# SBC_65C02_ISA_IRQ_v2.net
KiCad netlist of a schematic drawn in EAGLE
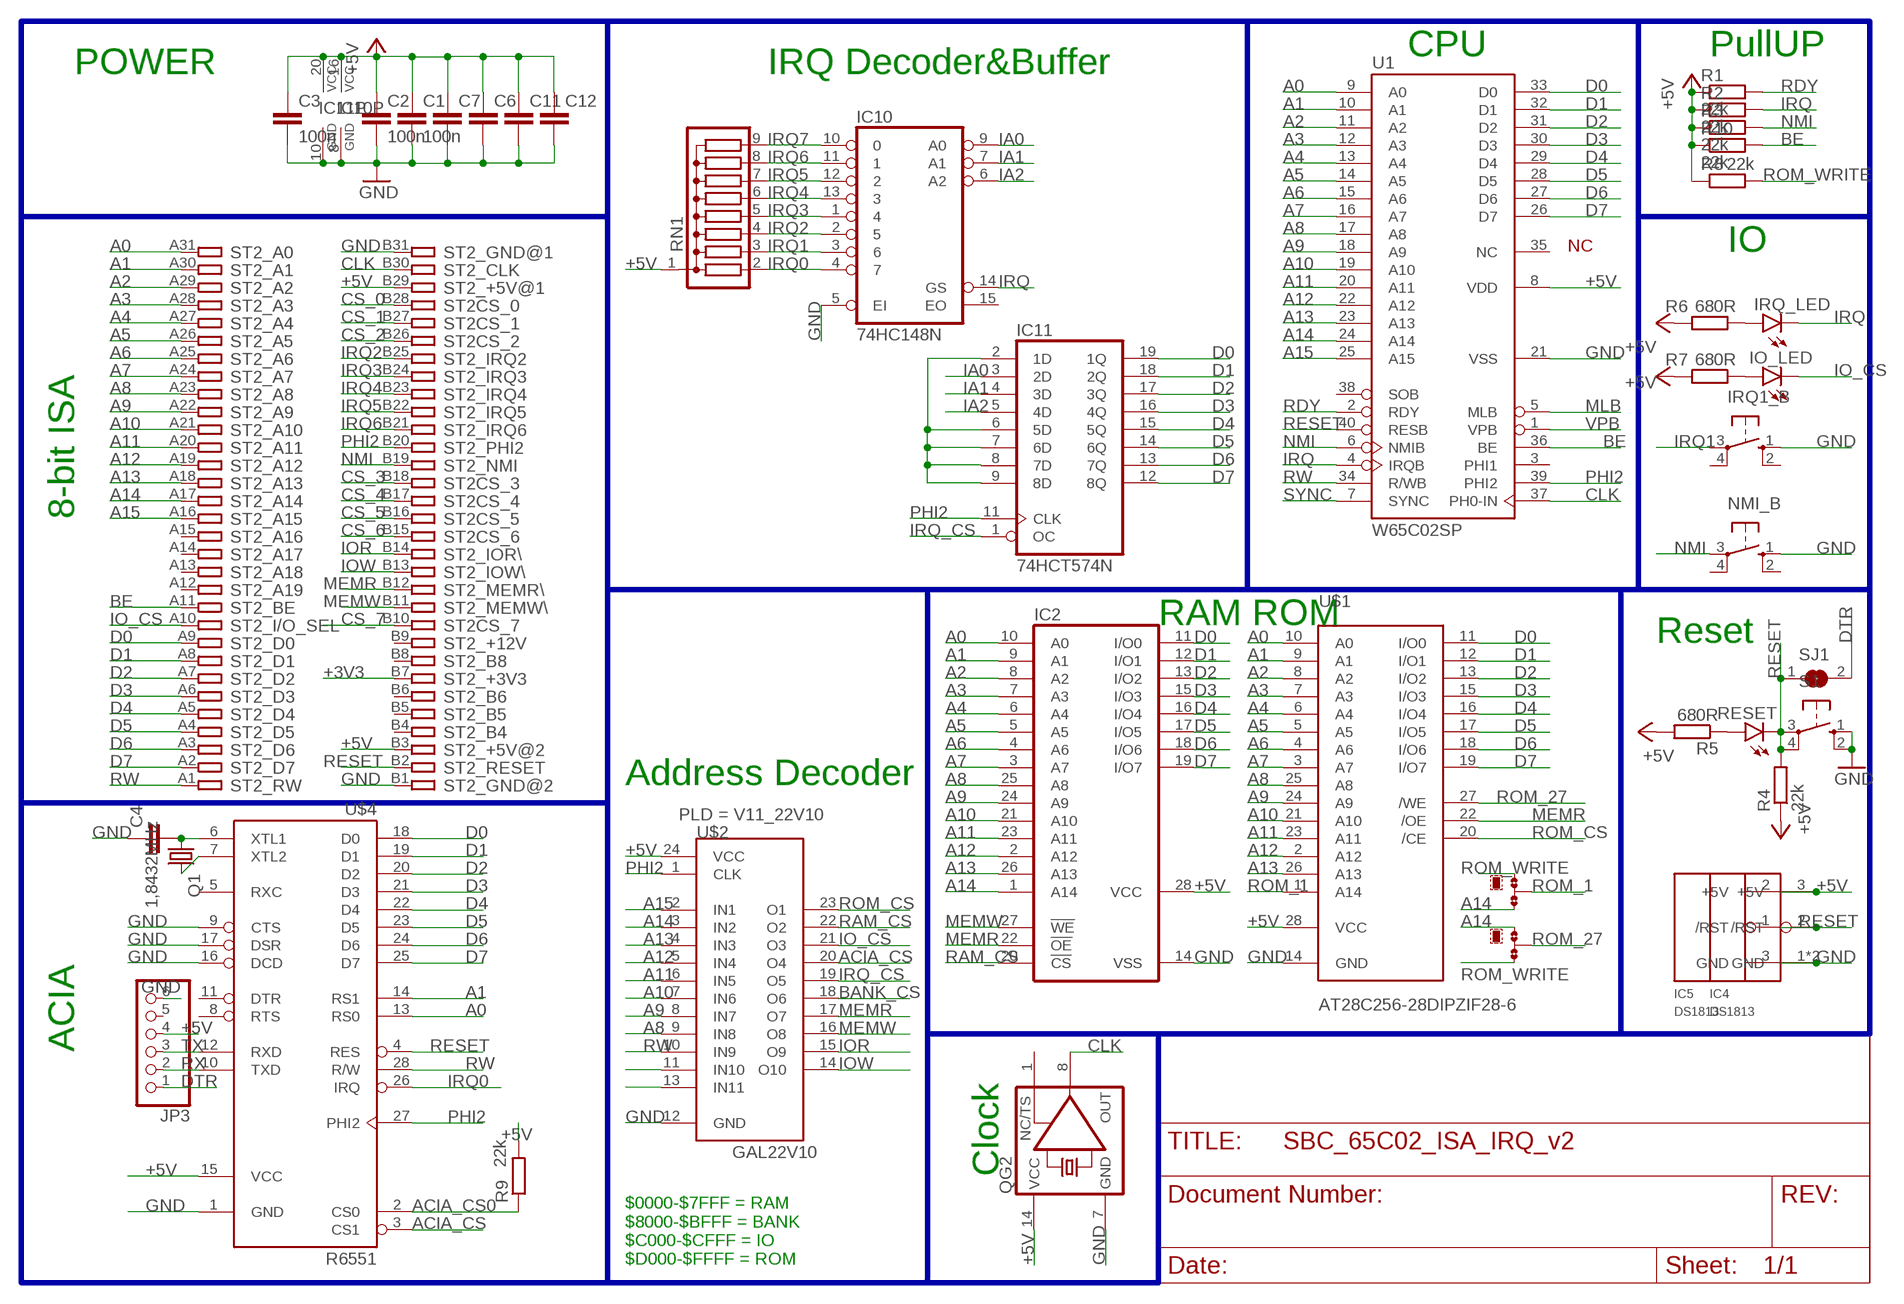
[diagram p0: schematic, sheet 1]

(export (version "E")
  (design (tool "Eeschema 10.0.6"))
  (components
    (comp (ref "C1")
      (value "100n")
      (footprint "eagle-import:C050-025X075")
      (libsource (lib "eagle-import") (part "C-EU050-025X075"))
    )
    (comp (ref "C2")
      (value "100n")
      (footprint "eagle-import:C050-025X075")
      (libsource (lib "eagle-import") (part "C-EU050-025X075"))
    )
    (comp (ref "C3")
      (value "100n")
      (footprint "eagle-import:C050-025X075")
      (libsource (lib "eagle-import") (part "C-EU050-025X075"))
    )
    (comp (ref "C4")
      (value "C-EU025-030X050")
      (footprint "eagle-import:C025-030X050")
      (libsource (lib "eagle-import") (part "rcl_334_C-EU025-030X050"))
    )
    (comp (ref "C6")
      (value "C-EU050-035X075")
      (footprint "eagle-import:C050-035X075")
      (libsource (lib "eagle-import") (part "rcl_334_C-EU050-035X075"))
    )
    (comp (ref "C7")
      (value "C-EU050-035X075")
      (footprint "eagle-import:C050-035X075")
      (libsource (lib "eagle-import") (part "rcl_334_C-EU050-035X075"))
    )
    (comp (ref "C11")
      (value "C-EU050-035X075")
      (footprint "eagle-import:C050-035X075")
      (libsource (lib "eagle-import") (part "rcl_334_C-EU050-035X075"))
    )
    (comp (ref "C12")
      (value "C-EU050-035X075")
      (footprint "eagle-import:C050-035X075")
      (libsource (lib "eagle-import") (part "rcl_334_C-EU050-035X075"))
    )
    (comp (ref "IC2")
      (value "62256P")
      (footprint "eagle-import:DIL28-6")
      (libsource (lib "eagle-import") (part "62256P"))
    )
    (comp (ref "IC4")
      (value "DS1813")
      (footprint "eagle-import:SOT223")
      (libsource (lib "eagle-import") (part "DS1813SOT-223"))
    )
    (comp (ref "IC5")
      (value "DS1813")
      (footprint "eagle-import:TO-92")
      (libsource (lib "eagle-import") (part "DS1813"))
    )
    (comp (ref "IC10")
      (value "74HC148N")
      (footprint "eagle-import:DIL16")
      (libsource (lib "eagle-import") (part "74148NHC"))
    )
    (comp (ref "IC11")
      (value "74HCT574N")
      (footprint "eagle-import:DIL20")
      (libsource (lib "eagle-import") (part "74574NHCT"))
    )
    (comp (ref "IO_LED")
      (value "LED5MM")
      (footprint "eagle-import:LED5MM")
      (libsource (lib "eagle-import") (part "LED5MM"))
    )
    (comp (ref "IRQ1_B")
      (value "10-XX")
      (footprint "eagle-import:B3F-10XX")
      (fields (field (name "MPN") "B3F-1000"))
      (libsource (lib "eagle-import") (part "10-XX"))
    )
    (comp (ref "IRQ_LED")
      (value "LED5MM")
      (footprint "eagle-import:LED5MM")
      (libsource (lib "eagle-import") (part "LED5MM"))
    )
    (comp (ref "JP3")
      (value "PINHD-1X6/90")
      (footprint "eagle-import:1X06_90")
      (libsource (lib "eagle-import") (part "PINHD-1X6/90"))
    )
    (comp (ref "NMI_B")
      (value "10-XX")
      (footprint "eagle-import:B3F-10XX")
      (fields (field (name "MPN") "B3F-1000"))
      (libsource (lib "eagle-import") (part "10-XX"))
    )
    (comp (ref "Q1")
      (value "1,8432MHz")
      (footprint "eagle-import:HC49_S")
      (libsource (lib "eagle-import") (part "CRYSTALHC49S"))
    )
    (comp (ref "QG2")
      (value "XO-14")
      (footprint "eagle-import:DIL14S")
      (libsource (lib "eagle-import") (part "XO-14"))
    )
    (comp (ref "R1")
      (value "22k")
      (footprint "eagle-import:0207_10")
      (libsource (lib "eagle-import") (part "R-EU_0207/10"))
    )
    (comp (ref "R2")
      (value "22k")
      (footprint "eagle-import:0207_10")
      (libsource (lib "eagle-import") (part "R-EU_0207/10"))
    )
    (comp (ref "R3")
      (value "22k")
      (footprint "eagle-import:0207_10")
      (libsource (lib "eagle-import") (part "R-EU_0207/10"))
    )
    (comp (ref "R4")
      (value "22k")
      (footprint "eagle-import:0207_10")
      (libsource (lib "eagle-import") (part "resistor_348_R-EU_0207/10"))
    )
    (comp (ref "R5")
      (value "680R")
      (footprint "eagle-import:0207_10")
      (libsource (lib "eagle-import") (part "resistor_348_R-EU_0207/10"))
    )
    (comp (ref "R6")
      (value "680R")
      (footprint "eagle-import:0207_10")
      (libsource (lib "eagle-import") (part "resistor_348_R-EU_0207/10"))
    )
    (comp (ref "R7")
      (value "680R")
      (footprint "eagle-import:0207_10")
      (libsource (lib "eagle-import") (part "resistor_348_R-EU_0207/10"))
    )
    (comp (ref "R8")
      (value "22k")
      (footprint "eagle-import:0207_10")
      (libsource (lib "eagle-import") (part "rcl_334_R-EU_0207/10"))
    )
    (comp (ref "R9")
      (value "22k")
      (footprint "eagle-import:0207_10")
      (libsource (lib "eagle-import") (part "rcl_334_R-EU_0207/10"))
    )
    (comp (ref "R10")
      (value "22k")
      (footprint "eagle-import:0207_10")
      (libsource (lib "eagle-import") (part "R-EU_0207/10"))
    )
    (comp (ref "RESET")
      (value "LED5MM")
      (footprint "eagle-import:LED5MM")
      (libsource (lib "eagle-import") (part "LED5MM"))
    )
    (comp (ref "RN1")
      (value "G08R")
      (footprint "eagle-import:SIL9")
      (libsource (lib "eagle-import") (part "G08R"))
    )
    (comp (ref "ROM_1")
      (value "0R-JUMPA")
      (footprint "eagle-import:A0R-JMP")
      (libsource (lib "eagle-import") (part "0R-JUMPA"))
    )
    (comp (ref "ROM_27")
      (value "0R-JUMPA")
      (footprint "eagle-import:A0R-JMP")
      (libsource (lib "eagle-import") (part "0R-JUMPA"))
    )
    (comp (ref "S1")
      (value "10-XX")
      (footprint "eagle-import:B3F-10XX")
      (fields (field (name "MPN") "B3F-1000"))
      (libsource (lib "eagle-import") (part "10-XX"))
    )
    (comp (ref "SJ1") (value "SJ") (footprint "eagle-import:SJ") (libsource (lib "eagle-import") (part "SJ")))
    (comp (ref "ST2")
      (value "IBM8BIT_ISASHORT")
      (footprint "eagle-import:APP_2X32_SHORT")
      (libsource (lib "eagle-import") (part "IBM8BIT_ISASHORT"))
    )
    (comp (ref "U$1")
      (value "AT28C256-28DIPZIF28-6")
      (footprint "eagle-import:228-1277-00-0602J")
      (libsource (lib "eagle-import") (part "AT28C256-28DIPZIF28-6"))
    )
    (comp (ref "U$2")
      (value "GAL22V10")
      (footprint "eagle-import:DIL28_1")
      (libsource (lib "eagle-import") (part "GAL22V10"))
    )
    (comp (ref "U$4")
      (value "R6551")
      (footprint "eagle-import:DIP-28")
      (libsource (lib "eagle-import") (part "R6551"))
    )
    (comp (ref "U1")
      (value "W65C02SP")
      (footprint "eagle-import:DIP-40")
      (libsource (lib "eagle-import") (part "W65C02SP"))
    )
  )
  (nets
    (net (code "1") (name "+5V") (class "Default")
      (node (ref "C1") (pin "1") (pinfunction "1_1") (pintype "passive"))
      (node (ref "C11") (pin "1") (pinfunction "1_1") (pintype "passive"))
      (node (ref "C12") (pin "1") (pinfunction "1_1") (pintype "passive"))
      (node (ref "C2") (pin "1") (pinfunction "1_1") (pintype "passive"))
      (node (ref "C3") (pin "1") (pinfunction "1_1") (pintype "passive"))
      (node (ref "C6") (pin "1") (pinfunction "1_1") (pintype "passive"))
      (node (ref "C7") (pin "1") (pinfunction "1_1") (pintype "passive"))
      (node (ref "IC10") (pin "16") (pinfunction "VCC_16") (pintype "power_in"))
      (node (ref "IC11") (pin "20") (pinfunction "VCC_20") (pintype "power_in"))
      (node (ref "IC2") (pin "28") (pinfunction "VCC_28") (pintype "power_in"))
      (node (ref "IC4") (pin "3") (pinfunction "+5V_3") (pintype "power_in"))
      (node (ref "IC5") (pin "2") (pinfunction "+5V_2") (pintype "power_in"))
      (node (ref "JP3") (pin "4") (pinfunction "4_4") (pintype "passive"))
      (node (ref "QG2") (pin "14") (pinfunction "VCC_14") (pintype "power_in"))
      (node (ref "R1") (pin "1") (pinfunction "1_1") (pintype "passive"))
      (node (ref "R10") (pin "1") (pinfunction "1_1") (pintype "passive"))
      (node (ref "R2") (pin "1") (pinfunction "1_1") (pintype "passive"))
      (node (ref "R3") (pin "1") (pinfunction "1_1") (pintype "passive"))
      (node (ref "R4") (pin "1") (pinfunction "1_1") (pintype "passive"))
      (node (ref "R5") (pin "2") (pinfunction "2_2") (pintype "passive"))
      (node (ref "R6") (pin "2") (pinfunction "2_2") (pintype "passive"))
      (node (ref "R7") (pin "2") (pinfunction "2_2") (pintype "passive"))
      (node (ref "R8") (pin "1") (pinfunction "1_1") (pintype "passive"))
      (node (ref "R9") (pin "2") (pinfunction "2_2") (pintype "passive"))
      (node (ref "RN1") (pin "1") (pinfunction "1_1") (pintype "passive"))
      (node (ref "ST2") (pin "B29") (pinfunction "P_B29") (pintype "bidirectional"))
      (node (ref "ST2") (pin "B3") (pinfunction "P_B3") (pintype "bidirectional"))
      (node (ref "U$1") (pin "28") (pinfunction "VCC_28") (pintype "bidirectional"))
      (node (ref "U$2") (pin "24") (pinfunction "VCC_24") (pintype "bidirectional"))
      (node (ref "U$4") (pin "15") (pinfunction "VCC_15") (pintype "power_in"))
      (node (ref "U1") (pin "8") (pinfunction "VDD_8") (pintype "power_in"))
    )
    (net (code "2") (name "/+3V3") (class "Default")
      (node (ref "ST2") (pin "B7") (pinfunction "P_B7") (pintype "bidirectional"))
    )
    (net (code "3") (name "/A0") (class "Default")
      (node (ref "IC2") (pin "10") (pinfunction "A0_10") (pintype "input"))
      (node (ref "ST2") (pin "A31") (pinfunction "P_A31") (pintype "bidirectional"))
      (node (ref "U$1") (pin "10") (pinfunction "A0_10") (pintype "bidirectional"))
      (node (ref "U$4") (pin "13") (pinfunction "RS0_13") (pintype "input"))
      (node (ref "U1") (pin "9") (pinfunction "A0_9") (pintype "bidirectional"))
    )
    (net (code "4") (name "/A1") (class "Default")
      (node (ref "IC2") (pin "9") (pinfunction "A1_9") (pintype "input"))
      (node (ref "ST2") (pin "A30") (pinfunction "P_A30") (pintype "bidirectional"))
      (node (ref "U$1") (pin "9") (pinfunction "A1_9") (pintype "bidirectional"))
      (node (ref "U$4") (pin "14") (pinfunction "RS1_14") (pintype "input"))
      (node (ref "U1") (pin "10") (pinfunction "A1_10") (pintype "bidirectional"))
    )
    (net (code "5") (name "/A2") (class "Default")
      (node (ref "IC2") (pin "8") (pinfunction "A2_8") (pintype "input"))
      (node (ref "ST2") (pin "A29") (pinfunction "P_A29") (pintype "bidirectional"))
      (node (ref "U$1") (pin "8") (pinfunction "A2_8") (pintype "bidirectional"))
      (node (ref "U1") (pin "11") (pinfunction "A2_11") (pintype "bidirectional"))
    )
    (net (code "6") (name "/A3") (class "Default")
      (node (ref "IC2") (pin "7") (pinfunction "A3_7") (pintype "input"))
      (node (ref "ST2") (pin "A28") (pinfunction "P_A28") (pintype "bidirectional"))
      (node (ref "U$1") (pin "7") (pinfunction "A3_7") (pintype "bidirectional"))
      (node (ref "U1") (pin "12") (pinfunction "A3_12") (pintype "bidirectional"))
    )
    (net (code "7") (name "/A4") (class "Default")
      (node (ref "IC2") (pin "6") (pinfunction "A4_6") (pintype "input"))
      (node (ref "ST2") (pin "A27") (pinfunction "P_A27") (pintype "bidirectional"))
      (node (ref "U$1") (pin "6") (pinfunction "A4_6") (pintype "bidirectional"))
      (node (ref "U1") (pin "13") (pinfunction "A4_13") (pintype "bidirectional"))
    )
    (net (code "8") (name "/A5") (class "Default")
      (node (ref "IC2") (pin "5") (pinfunction "A5_5") (pintype "input"))
      (node (ref "ST2") (pin "A26") (pinfunction "P_A26") (pintype "bidirectional"))
      (node (ref "U$1") (pin "5") (pinfunction "A5_5") (pintype "bidirectional"))
      (node (ref "U1") (pin "14") (pinfunction "A5_14") (pintype "bidirectional"))
    )
    (net (code "9") (name "/A6") (class "Default")
      (node (ref "IC2") (pin "4") (pinfunction "A6_4") (pintype "input"))
      (node (ref "ST2") (pin "A25") (pinfunction "P_A25") (pintype "bidirectional"))
      (node (ref "U$1") (pin "4") (pinfunction "A6_4") (pintype "bidirectional"))
      (node (ref "U1") (pin "15") (pinfunction "A6_15") (pintype "bidirectional"))
    )
    (net (code "10") (name "/A7") (class "Default")
      (node (ref "IC2") (pin "3") (pinfunction "A7_3") (pintype "input"))
      (node (ref "ST2") (pin "A24") (pinfunction "P_A24") (pintype "bidirectional"))
      (node (ref "U$1") (pin "3") (pinfunction "A7_3") (pintype "bidirectional"))
      (node (ref "U1") (pin "16") (pinfunction "A7_16") (pintype "bidirectional"))
    )
    (net (code "11") (name "/A8") (class "Default")
      (node (ref "IC2") (pin "25") (pinfunction "A8_25") (pintype "input"))
      (node (ref "ST2") (pin "A23") (pinfunction "P_A23") (pintype "bidirectional"))
      (node (ref "U$1") (pin "25") (pinfunction "A8_25") (pintype "bidirectional"))
      (node (ref "U$2") (pin "9") (pinfunction "IN8_9") (pintype "bidirectional"))
      (node (ref "U1") (pin "17") (pinfunction "A8_17") (pintype "bidirectional"))
    )
    (net (code "12") (name "/A9") (class "Default")
      (node (ref "IC2") (pin "24") (pinfunction "A9_24") (pintype "input"))
      (node (ref "ST2") (pin "A22") (pinfunction "P_A22") (pintype "bidirectional"))
      (node (ref "U$1") (pin "24") (pinfunction "A9_24") (pintype "bidirectional"))
      (node (ref "U$2") (pin "8") (pinfunction "IN7_8") (pintype "bidirectional"))
      (node (ref "U1") (pin "18") (pinfunction "A9_18") (pintype "bidirectional"))
    )
    (net (code "13") (name "/A10") (class "Default")
      (node (ref "IC2") (pin "21") (pinfunction "A10_21") (pintype "input"))
      (node (ref "ST2") (pin "A21") (pinfunction "P_A21") (pintype "bidirectional"))
      (node (ref "U$1") (pin "21") (pinfunction "A10_21") (pintype "bidirectional"))
      (node (ref "U$2") (pin "7") (pinfunction "IN6_7") (pintype "bidirectional"))
      (node (ref "U1") (pin "19") (pinfunction "A10_19") (pintype "bidirectional"))
    )
    (net (code "14") (name "/A11") (class "Default")
      (node (ref "IC2") (pin "23") (pinfunction "A11_23") (pintype "input"))
      (node (ref "ST2") (pin "A20") (pinfunction "P_A20") (pintype "bidirectional"))
      (node (ref "U$1") (pin "23") (pinfunction "A11_23") (pintype "bidirectional"))
      (node (ref "U$2") (pin "6") (pinfunction "IN5_6") (pintype "bidirectional"))
      (node (ref "U1") (pin "20") (pinfunction "A11_20") (pintype "bidirectional"))
    )
    (net (code "15") (name "/A12") (class "Default")
      (node (ref "IC2") (pin "2") (pinfunction "A12_2") (pintype "input"))
      (node (ref "ST2") (pin "A19") (pinfunction "P_A19") (pintype "bidirectional"))
      (node (ref "U$1") (pin "2") (pinfunction "A12_2") (pintype "bidirectional"))
      (node (ref "U$2") (pin "5") (pinfunction "IN4_5") (pintype "bidirectional"))
      (node (ref "U1") (pin "22") (pinfunction "A12_22") (pintype "bidirectional"))
    )
    (net (code "16") (name "/A13") (class "Default")
      (node (ref "IC2") (pin "26") (pinfunction "A13_26") (pintype "input"))
      (node (ref "ST2") (pin "A18") (pinfunction "P_A18") (pintype "bidirectional"))
      (node (ref "U$1") (pin "26") (pinfunction "A13_26") (pintype "bidirectional"))
      (node (ref "U$2") (pin "4") (pinfunction "IN3_4") (pintype "bidirectional"))
      (node (ref "U1") (pin "23") (pinfunction "A13_23") (pintype "bidirectional"))
    )
    (net (code "17") (name "/A14") (class "Default")
      (node (ref "IC2") (pin "1") (pinfunction "A14_1") (pintype "input"))
      (node (ref "ROM_1") (pin "3") (pinfunction "3_3") (pintype "passive"))
      (node (ref "ROM_27") (pin "1") (pinfunction "1_1") (pintype "passive"))
      (node (ref "ST2") (pin "A17") (pinfunction "P_A17") (pintype "bidirectional"))
      (node (ref "U$2") (pin "3") (pinfunction "IN2_3") (pintype "bidirectional"))
      (node (ref "U1") (pin "24") (pinfunction "A14_24") (pintype "bidirectional"))
    )
    (net (code "18") (name "/A15") (class "Default")
      (node (ref "ST2") (pin "A16") (pinfunction "P_A16") (pintype "bidirectional"))
      (node (ref "U$2") (pin "2") (pinfunction "IN1_2") (pintype "bidirectional"))
      (node (ref "U1") (pin "25") (pinfunction "A15_25") (pintype "bidirectional"))
    )
    (net (code "19") (name "/ACIA_CS") (class "Default")
      (node (ref "U$2") (pin "20") (pinfunction "O4_20") (pintype "bidirectional"))
      (node (ref "U$4") (pin "3") (pinfunction "CS1_3") (pintype "input"))
    )
    (net (code "20") (name "/ACIA_CS0") (class "Default")
      (node (ref "R9") (pin "1") (pinfunction "1_1") (pintype "passive"))
      (node (ref "U$4") (pin "2") (pinfunction "CS0_2") (pintype "input"))
    )
    (net (code "21") (name "/BANK_CS") (class "Default")
      (node (ref "U$2") (pin "18") (pinfunction "O6_18") (pintype "bidirectional"))
    )
    (net (code "22") (name "/BE") (class "Default")
      (node (ref "R10") (pin "2") (pinfunction "2_2") (pintype "passive"))
      (node (ref "ST2") (pin "A11") (pinfunction "P_A11") (pintype "bidirectional"))
      (node (ref "U1") (pin "36") (pinfunction "BE_36") (pintype "input"))
    )
    (net (code "23") (name "/CLK") (class "Default")
      (node (ref "QG2") (pin "8") (pinfunction "OUT_8") (pintype "output"))
      (node (ref "ST2") (pin "B30") (pinfunction "P_B30") (pintype "bidirectional"))
      (node (ref "U1") (pin "37") (pinfunction "PH0-IN_37") (pintype "input"))
    )
    (net (code "24") (name "/CS_0") (class "Default")
      (node (ref "ST2") (pin "B28") (pinfunction "P_B28") (pintype "bidirectional"))
    )
    (net (code "25") (name "/CS_1") (class "Default")
      (node (ref "ST2") (pin "B27") (pinfunction "P_B27") (pintype "bidirectional"))
    )
    (net (code "26") (name "/CS_2") (class "Default")
      (node (ref "ST2") (pin "B26") (pinfunction "P_B26") (pintype "bidirectional"))
    )
    (net (code "27") (name "/CS_3") (class "Default")
      (node (ref "ST2") (pin "B18") (pinfunction "P_B18") (pintype "bidirectional"))
    )
    (net (code "28") (name "/CS_4") (class "Default")
      (node (ref "ST2") (pin "B17") (pinfunction "P_B17") (pintype "bidirectional"))
    )
    (net (code "29") (name "/CS_5") (class "Default")
      (node (ref "ST2") (pin "B16") (pinfunction "P_B16") (pintype "bidirectional"))
    )
    (net (code "30") (name "/CS_6") (class "Default")
      (node (ref "ST2") (pin "B15") (pinfunction "P_B15") (pintype "bidirectional"))
    )
    (net (code "31") (name "/CS_7") (class "Default")
      (node (ref "ST2") (pin "B10") (pinfunction "P_B10") (pintype "bidirectional"))
    )
    (net (code "32") (name "/D0") (class "Default")
      (node (ref "IC11") (pin "19") (pinfunction "1Q_19") (pintype "tri_state"))
      (node (ref "IC2") (pin "11") (pinfunction "I/O0_11") (pintype "bidirectional"))
      (node (ref "ST2") (pin "A9") (pinfunction "P_A9") (pintype "bidirectional"))
      (node (ref "U$1") (pin "11") (pinfunction "I/O0_11") (pintype "bidirectional"))
      (node (ref "U$4") (pin "18") (pinfunction "D0_18") (pintype "bidirectional"))
      (node (ref "U1") (pin "33") (pinfunction "D0_33") (pintype "bidirectional"))
    )
    (net (code "33") (name "/D1") (class "Default")
      (node (ref "IC11") (pin "18") (pinfunction "2Q_18") (pintype "tri_state"))
      (node (ref "IC2") (pin "12") (pinfunction "I/O1_12") (pintype "bidirectional"))
      (node (ref "ST2") (pin "A8") (pinfunction "P_A8") (pintype "bidirectional"))
      (node (ref "U$1") (pin "12") (pinfunction "I/O1_12") (pintype "bidirectional"))
      (node (ref "U$4") (pin "19") (pinfunction "D1_19") (pintype "bidirectional"))
      (node (ref "U1") (pin "32") (pinfunction "D1_32") (pintype "bidirectional"))
    )
    (net (code "34") (name "/D2") (class "Default")
      (node (ref "IC11") (pin "17") (pinfunction "3Q_17") (pintype "tri_state"))
      (node (ref "IC2") (pin "13") (pinfunction "I/O2_13") (pintype "bidirectional"))
      (node (ref "ST2") (pin "A7") (pinfunction "P_A7") (pintype "bidirectional"))
      (node (ref "U$1") (pin "13") (pinfunction "I/O2_13") (pintype "bidirectional"))
      (node (ref "U$4") (pin "20") (pinfunction "D2_20") (pintype "bidirectional"))
      (node (ref "U1") (pin "31") (pinfunction "D2_31") (pintype "bidirectional"))
    )
    (net (code "35") (name "/D3") (class "Default")
      (node (ref "IC11") (pin "16") (pinfunction "4Q_16") (pintype "tri_state"))
      (node (ref "IC2") (pin "15") (pinfunction "I/O3_15") (pintype "bidirectional"))
      (node (ref "ST2") (pin "A6") (pinfunction "P_A6") (pintype "bidirectional"))
      (node (ref "U$1") (pin "15") (pinfunction "I/O3_15") (pintype "bidirectional"))
      (node (ref "U$4") (pin "21") (pinfunction "D3_21") (pintype "bidirectional"))
      (node (ref "U1") (pin "30") (pinfunction "D3_30") (pintype "bidirectional"))
    )
    (net (code "36") (name "/D4") (class "Default")
      (node (ref "IC11") (pin "15") (pinfunction "5Q_15") (pintype "tri_state"))
      (node (ref "IC2") (pin "16") (pinfunction "I/O4_16") (pintype "bidirectional"))
      (node (ref "ST2") (pin "A5") (pinfunction "P_A5") (pintype "bidirectional"))
      (node (ref "U$1") (pin "16") (pinfunction "I/O4_16") (pintype "bidirectional"))
      (node (ref "U$4") (pin "22") (pinfunction "D4_22") (pintype "bidirectional"))
      (node (ref "U1") (pin "29") (pinfunction "D4_29") (pintype "bidirectional"))
    )
    (net (code "37") (name "/D5") (class "Default")
      (node (ref "IC11") (pin "14") (pinfunction "6Q_14") (pintype "tri_state"))
      (node (ref "IC2") (pin "17") (pinfunction "I/O5_17") (pintype "bidirectional"))
      (node (ref "ST2") (pin "A4") (pinfunction "P_A4") (pintype "bidirectional"))
      (node (ref "U$1") (pin "17") (pinfunction "I/O5_17") (pintype "bidirectional"))
      (node (ref "U$4") (pin "23") (pinfunction "D5_23") (pintype "bidirectional"))
      (node (ref "U1") (pin "28") (pinfunction "D5_28") (pintype "bidirectional"))
    )
    (net (code "38") (name "/D6") (class "Default")
      (node (ref "IC11") (pin "13") (pinfunction "7Q_13") (pintype "tri_state"))
      (node (ref "IC2") (pin "18") (pinfunction "I/O6_18") (pintype "bidirectional"))
      (node (ref "ST2") (pin "A3") (pinfunction "P_A3") (pintype "bidirectional"))
      (node (ref "U$1") (pin "18") (pinfunction "I/O6_18") (pintype "bidirectional"))
      (node (ref "U$4") (pin "24") (pinfunction "D6_24") (pintype "bidirectional"))
      (node (ref "U1") (pin "27") (pinfunction "D6_27") (pintype "bidirectional"))
    )
    (net (code "39") (name "/D7") (class "Default")
      (node (ref "IC11") (pin "12") (pinfunction "8Q_12") (pintype "tri_state"))
      (node (ref "IC2") (pin "19") (pinfunction "I/O7_19") (pintype "bidirectional"))
      (node (ref "ST2") (pin "A2") (pinfunction "P_A2") (pintype "bidirectional"))
      (node (ref "U$1") (pin "19") (pinfunction "I/O7_19") (pintype "bidirectional"))
      (node (ref "U$4") (pin "25") (pinfunction "D7_25") (pintype "bidirectional"))
      (node (ref "U1") (pin "26") (pinfunction "D7_26") (pintype "bidirectional"))
    )
    (net (code "40") (name "/DTR") (class "Default")
      (node (ref "JP3") (pin "1") (pinfunction "1_1") (pintype "passive"))
      (node (ref "SJ1") (pin "2") (pinfunction "2_2") (pintype "passive"))
    )
    (net (code "41") (name "/IA0") (class "Default")
      (node (ref "IC10") (pin "9") (pinfunction "A0_9") (pintype "output"))
      (node (ref "IC11") (pin "3") (pinfunction "2D_3") (pintype "input"))
    )
    (net (code "42") (name "/IA1") (class "Default")
      (node (ref "IC10") (pin "7") (pinfunction "A1_7") (pintype "output"))
      (node (ref "IC11") (pin "4") (pinfunction "3D_4") (pintype "input"))
    )
    (net (code "43") (name "/IA2") (class "Default")
      (node (ref "IC10") (pin "6") (pinfunction "A2_6") (pintype "output"))
      (node (ref "IC11") (pin "5") (pinfunction "4D_5") (pintype "input"))
    )
    (net (code "44") (name "/IOR") (class "Default")
      (node (ref "ST2") (pin "B14") (pinfunction "P_B14") (pintype "bidirectional"))
      (node (ref "U$2") (pin "15") (pinfunction "O9_15") (pintype "bidirectional"))
    )
    (net (code "45") (name "/IOW") (class "Default")
      (node (ref "ST2") (pin "B13") (pinfunction "P_B13") (pintype "bidirectional"))
      (node (ref "U$2") (pin "14") (pinfunction "O10_14") (pintype "bidirectional"))
    )
    (net (code "46") (name "/IO_CS") (class "Default")
      (node (ref "IO_LED") (pin "K") (pinfunction "C_K") (pintype "passive"))
      (node (ref "ST2") (pin "A10") (pinfunction "P_A10") (pintype "bidirectional"))
      (node (ref "U$2") (pin "21") (pinfunction "O3_21") (pintype "bidirectional"))
    )
    (net (code "47") (name "/IRQ") (class "Default")
      (node (ref "IC10") (pin "14") (pinfunction "GS_14") (pintype "output"))
      (node (ref "IRQ_LED") (pin "K") (pinfunction "C_K") (pintype "passive"))
      (node (ref "R2") (pin "2") (pinfunction "2_2") (pintype "passive"))
      (node (ref "U1") (pin "4") (pinfunction "IRQB_4") (pintype "input"))
    )
    (net (code "48") (name "/IRQ0") (class "Default")
      (node (ref "IC10") (pin "4") (pinfunction "7_4") (pintype "input"))
      (node (ref "RN1") (pin "2") (pinfunction "2_2") (pintype "passive"))
      (node (ref "U$4") (pin "26") (pinfunction "IRQ_26") (pintype "output"))
    )
    (net (code "49") (name "/IRQ1") (class "Default")
      (node (ref "IC10") (pin "3") (pinfunction "6_3") (pintype "input"))
      (node (ref "IRQ1_B") (pin "3") (pinfunction "P_3") (pintype "passive"))
      (node (ref "RN1") (pin "3") (pinfunction "3_3") (pintype "passive"))
    )
    (net (code "50") (name "/IRQ2") (class "Default")
      (node (ref "IC10") (pin "2") (pinfunction "5_2") (pintype "input"))
      (node (ref "RN1") (pin "4") (pinfunction "4_4") (pintype "passive"))
      (node (ref "ST2") (pin "B25") (pinfunction "P_B25") (pintype "bidirectional"))
    )
    (net (code "51") (name "/IRQ3") (class "Default")
      (node (ref "IC10") (pin "1") (pinfunction "4_1") (pintype "input"))
      (node (ref "RN1") (pin "5") (pinfunction "5_5") (pintype "passive"))
      (node (ref "ST2") (pin "B24") (pinfunction "P_B24") (pintype "bidirectional"))
    )
    (net (code "52") (name "/IRQ4") (class "Default")
      (node (ref "IC10") (pin "13") (pinfunction "3_13") (pintype "input"))
      (node (ref "RN1") (pin "6") (pinfunction "6_6") (pintype "passive"))
      (node (ref "ST2") (pin "B23") (pinfunction "P_B23") (pintype "bidirectional"))
    )
    (net (code "53") (name "/IRQ5") (class "Default")
      (node (ref "IC10") (pin "12") (pinfunction "2_12") (pintype "input"))
      (node (ref "RN1") (pin "7") (pinfunction "7_7") (pintype "passive"))
      (node (ref "ST2") (pin "B22") (pinfunction "P_B22") (pintype "bidirectional"))
    )
    (net (code "54") (name "/IRQ6") (class "Default")
      (node (ref "IC10") (pin "11") (pinfunction "1_11") (pintype "input"))
      (node (ref "RN1") (pin "8") (pinfunction "8_8") (pintype "passive"))
      (node (ref "ST2") (pin "B21") (pinfunction "P_B21") (pintype "bidirectional"))
    )
    (net (code "55") (name "/IRQ7") (class "Default")
      (node (ref "IC10") (pin "10") (pinfunction "0_10") (pintype "input"))
      (node (ref "RN1") (pin "9") (pinfunction "9_9") (pintype "passive"))
    )
    (net (code "56") (name "/IRQ_CS") (class "Default")
      (node (ref "IC11") (pin "1") (pinfunction "OC_1") (pintype "input"))
      (node (ref "U$2") (pin "19") (pinfunction "O5_19") (pintype "bidirectional"))
    )
    (net (code "57") (name "/MEMR") (class "Default")
      (node (ref "IC2") (pin "22") (pinfunction "~{OE}_22") (pintype "input"))
      (node (ref "ST2") (pin "B12") (pinfunction "P_B12") (pintype "bidirectional"))
      (node (ref "U$1") (pin "22") (pinfunction "/OE_22") (pintype "bidirectional"))
      (node (ref "U$2") (pin "17") (pinfunction "O7_17") (pintype "bidirectional"))
    )
    (net (code "58") (name "/MEMW") (class "Default")
      (node (ref "IC2") (pin "27") (pinfunction "~{WE}_27") (pintype "input"))
      (node (ref "ST2") (pin "B11") (pinfunction "P_B11") (pintype "bidirectional"))
      (node (ref "U$2") (pin "16") (pinfunction "O8_16") (pintype "bidirectional"))
    )
    (net (code "59") (name "/MLB") (class "Default")
      (node (ref "U1") (pin "5") (pinfunction "MLB_5") (pintype "output"))
    )
    (net (code "60") (name "/NMI") (class "Default")
      (node (ref "NMI_B") (pin "3") (pinfunction "P_3") (pintype "passive"))
      (node (ref "R3") (pin "2") (pinfunction "2_2") (pintype "passive"))
      (node (ref "ST2") (pin "B19") (pinfunction "P_B19") (pintype "bidirectional"))
      (node (ref "U1") (pin "6") (pinfunction "NMIB_6") (pintype "input"))
    )
    (net (code "61") (name "/PHI2") (class "Default")
      (node (ref "IC11") (pin "11") (pinfunction "CLK_11") (pintype "input"))
      (node (ref "ST2") (pin "B20") (pinfunction "P_B20") (pintype "bidirectional"))
      (node (ref "U$2") (pin "1") (pinfunction "CLK_1") (pintype "bidirectional"))
      (node (ref "U$4") (pin "27") (pinfunction "PHI2_27") (pintype "input"))
      (node (ref "U1") (pin "39") (pinfunction "PHI2_39") (pintype "output"))
    )
    (net (code "62") (name "/RAM_CS") (class "Default")
      (node (ref "IC2") (pin "20") (pinfunction "~{CS}_20") (pintype "input"))
      (node (ref "U$2") (pin "22") (pinfunction "O2_22") (pintype "bidirectional"))
    )
    (net (code "63") (name "/RDY") (class "Default")
      (node (ref "R1") (pin "2") (pinfunction "2_2") (pintype "passive"))
      (node (ref "U1") (pin "2") (pinfunction "RDY_2") (pintype "bidirectional"))
    )
    (net (code "64") (name "/RESET") (class "Default")
      (node (ref "IC4") (pin "2") (pinfunction "/RST_2") (pintype "passive"))
      (node (ref "IC5") (pin "1") (pinfunction "/RST_1") (pintype "passive"))
      (node (ref "R4") (pin "2") (pinfunction "2_2") (pintype "passive"))
      (node (ref "RESET") (pin "K") (pinfunction "C_K") (pintype "passive"))
      (node (ref "S1") (pin "3") (pinfunction "P_3") (pintype "passive"))
      (node (ref "S1") (pin "4") (pinfunction "P1_4") (pintype "passive"))
      (node (ref "SJ1") (pin "1") (pinfunction "1_1") (pintype "passive"))
      (node (ref "ST2") (pin "B2") (pinfunction "P_B2") (pintype "bidirectional"))
      (node (ref "U$4") (pin "4") (pinfunction "RES_4") (pintype "input"))
      (node (ref "U1") (pin "40") (pinfunction "RESB_40") (pintype "input"))
    )
    (net (code "65") (name "/ROM_1") (class "Default")
      (node (ref "ROM_1") (pin "2") (pinfunction "2_2") (pintype "passive"))
      (node (ref "U$1") (pin "1") (pinfunction "A14_1") (pintype "bidirectional"))
    )
    (net (code "66") (name "/ROM_27") (class "Default")
      (node (ref "ROM_27") (pin "2") (pinfunction "2_2") (pintype "passive"))
      (node (ref "U$1") (pin "27") (pinfunction "/WE_27") (pintype "bidirectional"))
    )
    (net (code "67") (name "/ROM_CS") (class "Default")
      (node (ref "U$1") (pin "20") (pinfunction "/CE_20") (pintype "bidirectional"))
      (node (ref "U$2") (pin "23") (pinfunction "O1_23") (pintype "bidirectional"))
    )
    (net (code "68") (name "/ROM_WRITE") (class "Default")
      (node (ref "R8") (pin "2") (pinfunction "2_2") (pintype "passive"))
      (node (ref "ROM_1") (pin "1") (pinfunction "1_1") (pintype "passive"))
      (node (ref "ROM_27") (pin "3") (pinfunction "3_3") (pintype "passive"))
    )
    (net (code "69") (name "/RW") (class "Default")
      (node (ref "ST2") (pin "A1") (pinfunction "P_A1") (pintype "bidirectional"))
      (node (ref "U$2") (pin "10") (pinfunction "IN9_10") (pintype "bidirectional"))
      (node (ref "U$4") (pin "28") (pinfunction "R/W_28") (pintype "input"))
      (node (ref "U1") (pin "34") (pinfunction "R/WB_34") (pintype "output"))
    )
    (net (code "70") (name "/RX") (class "Default")
      (node (ref "JP3") (pin "2") (pinfunction "2_2") (pintype "passive"))
      (node (ref "U$4") (pin "10") (pinfunction "TXD_10") (pintype "output"))
    )
    (net (code "71") (name "/SYNC") (class "Default")
      (node (ref "U1") (pin "7") (pinfunction "SYNC_7") (pintype "output"))
    )
    (net (code "72") (name "/TX") (class "Default")
      (node (ref "JP3") (pin "3") (pinfunction "3_3") (pintype "passive"))
      (node (ref "U$4") (pin "12") (pinfunction "RXD_12") (pintype "input"))
    )
    (net (code "73") (name "/VPB") (class "Default")
      (node (ref "U1") (pin "1") (pinfunction "VPB_1") (pintype "output"))
    )
    (net (code "74") (name "GND") (class "Default")
      (node (ref "C1") (pin "2") (pinfunction "2_2") (pintype "passive"))
      (node (ref "C11") (pin "2") (pinfunction "2_2") (pintype "passive"))
      (node (ref "C12") (pin "2") (pinfunction "2_2") (pintype "passive"))
      (node (ref "C2") (pin "2") (pinfunction "2_2") (pintype "passive"))
      (node (ref "C3") (pin "2") (pinfunction "2_2") (pintype "passive"))
      (node (ref "C4") (pin "1") (pinfunction "1_1") (pintype "passive"))
      (node (ref "C6") (pin "2") (pinfunction "2_2") (pintype "passive"))
      (node (ref "C7") (pin "2") (pinfunction "2_2") (pintype "passive"))
      (node (ref "IC10") (pin "5") (pinfunction "EI_5") (pintype "input"))
      (node (ref "IC10") (pin "8") (pinfunction "GND_8") (pintype "power_in"))
      (node (ref "IC11") (pin "10") (pinfunction "GND_10") (pintype "power_in"))
      (node (ref "IC2") (pin "14") (pinfunction "VSS_14") (pintype "power_in"))
      (node (ref "IC4") (pin "1") (pinfunction "GND_1") (pintype "power_in"))
      (node (ref "IC4") (pin "4") (pinfunction "GND_4") (pintype "power_in"))
      (node (ref "IC5") (pin "3") (pinfunction "GND_3") (pintype "power_in"))
      (node (ref "IRQ1_B") (pin "1") (pinfunction "S_1") (pintype "passive"))
      (node (ref "JP3") (pin "6") (pinfunction "6_6") (pintype "passive"))
      (node (ref "NMI_B") (pin "1") (pinfunction "S_1") (pintype "passive"))
      (node (ref "QG2") (pin "7") (pinfunction "GND_7") (pintype "power_in"))
      (node (ref "S1") (pin "1") (pinfunction "S_1") (pintype "passive"))
      (node (ref "S1") (pin "2") (pinfunction "S1_2") (pintype "passive"))
      (node (ref "ST2") (pin "B1") (pinfunction "P_B1") (pintype "bidirectional"))
      (node (ref "ST2") (pin "B31") (pinfunction "P_B31") (pintype "bidirectional"))
      (node (ref "U$1") (pin "14") (pinfunction "GND_14") (pintype "bidirectional"))
      (node (ref "U$2") (pin "12") (pinfunction "GND_12") (pintype "bidirectional"))
      (node (ref "U$4") (pin "1") (pinfunction "GND_1") (pintype "power_in"))
      (node (ref "U$4") (pin "16") (pinfunction "DCD_16") (pintype "input"))
      (node (ref "U$4") (pin "17") (pinfunction "DSR_17") (pintype "input"))
      (node (ref "U$4") (pin "9") (pinfunction "CTS_9") (pintype "input"))
      (node (ref "U1") (pin "21") (pinfunction "VSS_21") (pintype "power_in"))
    )
    (net (code "75") (name "Net-(IC11A-1D)") (class "Default")
      (node (ref "IC11") (pin "2") (pinfunction "1D_2") (pintype "input"))
      (node (ref "IC11") (pin "6") (pinfunction "5D_6") (pintype "input"))
      (node (ref "IC11") (pin "7") (pinfunction "6D_7") (pintype "input"))
      (node (ref "IC11") (pin "8") (pinfunction "7D_8") (pintype "input"))
      (node (ref "IC11") (pin "9") (pinfunction "8D_9") (pintype "input"))
    )
    (net (code "76") (name "Net-(IO_LED-PadA)") (class "Default")
      (node (ref "IO_LED") (pin "A") (pinfunction "A_A") (pintype "passive"))
      (node (ref "R7") (pin "1") (pinfunction "1_1") (pintype "passive"))
    )
    (net (code "77") (name "Net-(IRQ_LED-PadA)") (class "Default")
      (node (ref "IRQ_LED") (pin "A") (pinfunction "A_A") (pintype "passive"))
      (node (ref "R6") (pin "1") (pinfunction "1_1") (pintype "passive"))
    )
    (net (code "78") (name "Net-(R5-Pad1)") (class "Default")
      (node (ref "R5") (pin "1") (pinfunction "1_1") (pintype "passive"))
      (node (ref "RESET") (pin "A") (pinfunction "A_A") (pintype "passive"))
    )
    (net (code "79") (name "Net-(U$4-XTL1)") (class "Default")
      (node (ref "C4") (pin "2") (pinfunction "2_2") (pintype "passive"))
      (node (ref "Q1") (pin "1") (pinfunction "1_1") (pintype "passive"))
      (node (ref "U$4") (pin "6") (pinfunction "XTL1_6") (pintype "input"))
    )
    (net (code "80") (name "Net-(U$4-XTL2)") (class "Default")
      (node (ref "Q1") (pin "2") (pinfunction "2_2") (pintype "passive"))
      (node (ref "U$4") (pin "7") (pinfunction "XTL2_7") (pintype "output"))
    )
    (net (code "81") (name "unconnected-(IC10A-EO-Pad15)") (class "Default")
      (node (ref "IC10") (pin "15") (pinfunction "EO_15") (pintype "output"))
    )
    (net (code "82") (name "unconnected-(IRQ1_B-P1-Pad4)") (class "Default")
      (node (ref "IRQ1_B") (pin "4") (pinfunction "P1_4") (pintype "passive"))
    )
    (net (code "83") (name "unconnected-(IRQ1_B-S1-Pad2)") (class "Default")
      (node (ref "IRQ1_B") (pin "2") (pinfunction "S1_2") (pintype "passive"))
    )
    (net (code "84") (name "unconnected-(JP3-Pad5)") (class "Default")
      (node (ref "JP3") (pin "5") (pinfunction "5_5") (pintype "passive"))
    )
    (net (code "85") (name "unconnected-(NMI_B-P1-Pad4)") (class "Default")
      (node (ref "NMI_B") (pin "4") (pinfunction "P1_4") (pintype "passive"))
    )
    (net (code "86") (name "unconnected-(NMI_B-S1-Pad2)") (class "Default")
      (node (ref "NMI_B") (pin "2") (pinfunction "S1_2") (pintype "passive"))
    )
    (net (code "87") (name "unconnected-(QG2-TS-Pad1)") (class "Default")
      (node (ref "QG2") (pin "1") (pinfunction "TS_1") (pintype "passive"))
    )
    (net (code "88") (name "unconnected-(ST2AG-P-PadB4)") (class "Default")
      (node (ref "ST2") (pin "B4") (pinfunction "P_B4") (pintype "bidirectional"))
    )
    (net (code "89") (name "unconnected-(ST2AH-P-PadB5)") (class "Default")
      (node (ref "ST2") (pin "B5") (pinfunction "P_B5") (pintype "bidirectional"))
    )
    (net (code "90") (name "unconnected-(ST2AI-P-PadB6)") (class "Default")
      (node (ref "ST2") (pin "B6") (pinfunction "P_B6") (pintype "bidirectional"))
    )
    (net (code "91") (name "unconnected-(ST2AJ-P-PadB8)") (class "Default")
      (node (ref "ST2") (pin "B8") (pinfunction "P_B8") (pintype "bidirectional"))
    )
    (net (code "92") (name "unconnected-(ST2I-P-PadB9)") (class "Default")
      (node (ref "ST2") (pin "B9") (pinfunction "P_B9") (pintype "bidirectional"))
    )
    (net (code "93") (name "unconnected-(ST2U-P-PadA15)") (class "Default")
      (node (ref "ST2") (pin "A15") (pinfunction "P_A15") (pintype "bidirectional"))
    )
    (net (code "94") (name "unconnected-(ST2V-P-PadA14)") (class "Default")
      (node (ref "ST2") (pin "A14") (pinfunction "P_A14") (pintype "bidirectional"))
    )
    (net (code "95") (name "unconnected-(ST2W-P-PadA13)") (class "Default")
      (node (ref "ST2") (pin "A13") (pinfunction "P_A13") (pintype "bidirectional"))
    )
    (net (code "96") (name "unconnected-(ST2X-P-PadA12)") (class "Default")
      (node (ref "ST2") (pin "A12") (pinfunction "P_A12") (pintype "bidirectional"))
    )
    (net (code "97") (name "unconnected-(U$2-IN10-Pad11)") (class "Default")
      (node (ref "U$2") (pin "11") (pinfunction "IN10_11") (pintype "bidirectional"))
    )
    (net (code "98") (name "unconnected-(U$2-IN11-Pad13)") (class "Default")
      (node (ref "U$2") (pin "13") (pinfunction "IN11_13") (pintype "bidirectional"))
    )
    (net (code "99") (name "unconnected-(U$4-DTR-Pad11)") (class "Default")
      (node (ref "U$4") (pin "11") (pinfunction "DTR_11") (pintype "output"))
    )
    (net (code "100") (name "unconnected-(U$4-RTS-Pad8)") (class "Default")
      (node (ref "U$4") (pin "8") (pinfunction "RTS_8") (pintype "output"))
    )
    (net (code "101") (name "unconnected-(U$4-RXC-Pad5)") (class "Default")
      (node (ref "U$4") (pin "5") (pinfunction "RXC_5") (pintype "bidirectional"))
    )
    (net (code "102") (name "unconnected-(U1-NC-Pad35)") (class "Default")
      (node (ref "U1") (pin "35") (pinfunction "NC_35") (pintype "no_connect"))
    )
    (net (code "103") (name "unconnected-(U1-PHI1-Pad3)") (class "Default")
      (node (ref "U1") (pin "3") (pinfunction "PHI1_3") (pintype "output"))
    )
    (net (code "104") (name "unconnected-(U1-SOB-Pad38)") (class "Default")
      (node (ref "U1") (pin "38") (pinfunction "SOB_38") (pintype "input"))
    )
  )
)
